# Sheet1.net
KiCad netlist of a schematic drawn in Altium Designer
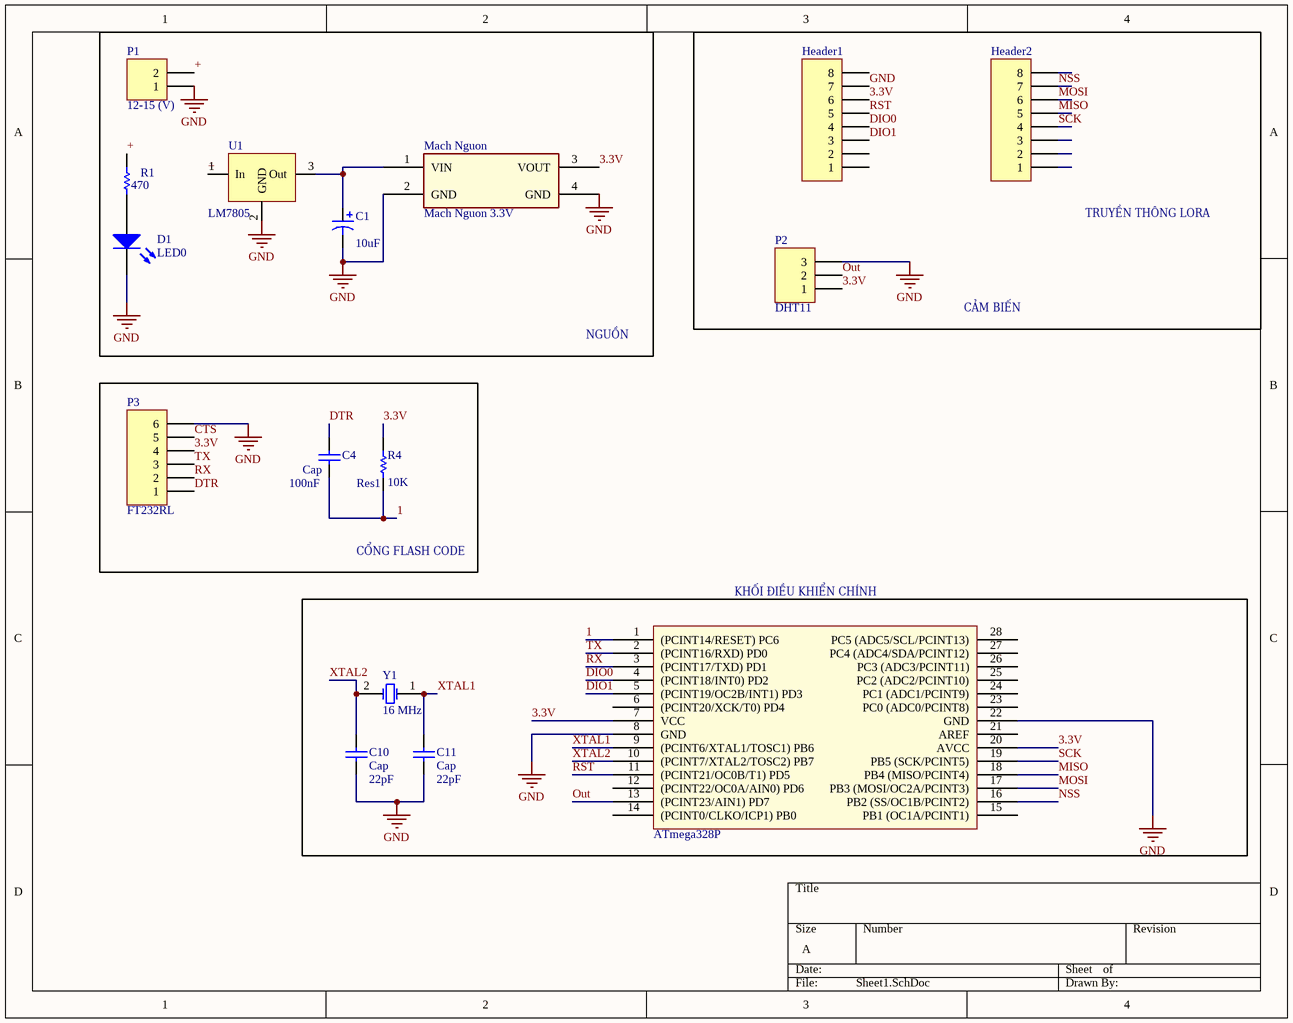
[diagram p0: Sheet1.SchDoc]

(export (version "E")
  (design (tool "Eeschema 10.0.6"))
  (components
    (comp (ref "ATmega328P")
      (value "ATmega328P")
      (footprint "DIP794W46P254L2967H457Q28B")
      (libsource (lib "ATMEGA328") (part "ATmega328P"))
    )
    (comp (ref "C1")
      (value "10uF")
      (footprint "RB7.6-15")
      (description "Polarized Capacitor (Radial)")
      (fields (field (name "Comment") "Cap Pol1") (field (name "PUBLISHER") "Altium Limited"))
      (libsource (lib "Miscellaneous Devices") (part "Cap Pol1"))
    )
    (comp (ref "C4")
      (value "Cap")
      (footprint "RAD-0.3")
      (description "Capacitor")
      (fields (field (name "ALTIUM_VALUE") "100nF") (field (name "PUBLISHER") "Altium Limited"))
      (libsource (lib "Miscellaneous Devices") (part "Cap"))
    )
    (comp (ref "C10")
      (value "Cap")
      (footprint "RAD-0.3")
      (description "Capacitor")
      (fields (field (name "ALTIUM_VALUE") "22pF") (field (name "PUBLISHER") "Altium Limited"))
      (libsource (lib "Miscellaneous Devices") (part "Cap"))
    )
    (comp (ref "C11")
      (value "Cap")
      (footprint "RAD-0.3")
      (description "Capacitor")
      (fields (field (name "ALTIUM_VALUE") "22pF") (field (name "PUBLISHER") "Altium Limited"))
      (libsource (lib "Miscellaneous Devices") (part "Cap"))
    )
    (comp (ref "D1")
      (value "LED0")
      (footprint "LED-0")
      (description "Typical INFRARED GaAs LED")
      (fields (field (name "PUBLISHER") "Altium Limited"))
      (libsource (lib "Miscellaneous Devices") (part "LED0"))
    )
    (comp (ref "Header1")
      (value "~")
      (footprint "HDR1X8")
      (description "Header, 8-Pin")
      (fields (field (name "PUBLISHER") "Altium Limited"))
      (libsource (lib "Miscellaneous Connectors") (part "Header 8"))
    )
    (comp (ref "Header2")
      (value "~")
      (footprint "HDR1X8")
      (description "Header, 8-Pin")
      (fields (field (name "PUBLISHER") "Altium Limited"))
      (libsource (lib "Miscellaneous Connectors") (part "Header 8"))
    )
    (comp (ref "Mach Nguon")
      (value "Mach Nguon 3.3V")
      (footprint "PCBComponent_1")
      (libsource (lib "MachNguon3.3V") (part "Component_1"))
    )
    (comp (ref "P1")
      (value "12-15 (V)")
      (footprint "HDR1X2")
      (description "Header, 2-Pin")
      (fields (field (name "PUBLISHER") "Altium Limited"))
      (libsource (lib "Miscellaneous Connectors") (part "Header 2"))
    )
    (comp (ref "P2")
      (value "DHT11")
      (footprint "HDR1X3")
      (description "Header, 3-Pin")
      (fields (field (name "PUBLISHER") "Altium Limited"))
      (libsource (lib "Miscellaneous Connectors") (part "Header 3"))
    )
    (comp (ref "P3")
      (value "FT232RL")
      (footprint "HDR1X6")
      (description "Header, 6-Pin")
      (fields (field (name "PUBLISHER") "Altium Limited"))
      (libsource (lib "Miscellaneous Connectors") (part "Header 6"))
    )
    (comp (ref "R1")
      (value "470")
      (footprint "AXIAL-0.3")
      (description "Resistor")
      (fields (field (name "Comment") "Res1") (field (name "PUBLISHER") "Altium Limited"))
      (libsource (lib "Miscellaneous Devices") (part "Res1"))
    )
    (comp (ref "R4")
      (value "Res1")
      (footprint "AXIAL-0.3")
      (description "Resistor")
      (fields (field (name "ALTIUM_VALUE") "10K") (field (name "PUBLISHER") "Altium Limited"))
      (libsource (lib "Miscellaneous Devices") (part "Res1"))
    )
    (comp (ref "U1")
      (value "LM7805")
      (footprint "TO92-")
      (description "IC REG LIN 5V 1A")
      (libsource (lib "LM7805") (part "LM7805"))
    )
    (comp (ref "Y1")
      (value "16 MHz")
      (footprint "R38")
      (description "Crystal Oscillator")
      (fields (field (name "PUBLISHER") "Altium Limited"))
      (libsource (lib "Miscellaneous Devices") (part "XTAL"))
    )
  )
  (nets
    (net (code "1") (name "/+") (class "Default")
      (node (ref "P1") (pin "2") (pinfunction "2_2") (pintype "passive"))
      (node (ref "R1") (pin "2") (pinfunction "2_2") (pintype "passive"))
      (node (ref "U1") (pin "1") (pinfunction "In_1") (pintype "passive"))
    )
    (net (code "2") (name "/1") (class "Default")
      (node (ref "ATmega328P") (pin "1") (pinfunction "(PCINT14/RESET)_PC6_1") (pintype "passive"))
      (node (ref "C4") (pin "1") (pinfunction "1_1") (pintype "passive"))
      (node (ref "R4") (pin "1") (pinfunction "1_1") (pintype "passive"))
    )
    (net (code "3") (name "/3.3V") (class "Default")
      (node (ref "ATmega328P") (pin "20") (pinfunction "AVCC_20") (pintype "passive"))
      (node (ref "ATmega328P") (pin "7") (pinfunction "VCC_7") (pintype "passive"))
      (node (ref "Header1") (pin "6") (pinfunction "6_6") (pintype "passive"))
      (node (ref "Mach Nguon") (pin "3") (pinfunction "VOUT_3") (pintype "passive"))
      (node (ref "P2") (pin "1") (pinfunction "1_1") (pintype "passive"))
      (node (ref "P3") (pin "4") (pinfunction "4_4") (pintype "passive"))
      (node (ref "R4") (pin "2") (pinfunction "2_2") (pintype "passive"))
    )
    (net (code "4") (name "/CTS") (class "Default")
      (node (ref "P3") (pin "5") (pinfunction "5_5") (pintype "passive"))
    )
    (net (code "5") (name "/DIO0") (class "Default")
      (node (ref "ATmega328P") (pin "4") (pinfunction "(PCINT18/INT0)_PD2_4") (pintype "passive"))
      (node (ref "Header1") (pin "4") (pinfunction "4_4") (pintype "passive"))
    )
    (net (code "6") (name "/DIO1") (class "Default")
      (node (ref "ATmega328P") (pin "5") (pinfunction "(PCINT19/OC2B/INT1)_PD3_5") (pintype "passive"))
      (node (ref "Header1") (pin "3") (pinfunction "3_3") (pintype "passive"))
    )
    (net (code "7") (name "/DTR") (class "Default")
      (node (ref "C4") (pin "2") (pinfunction "2_2") (pintype "passive"))
      (node (ref "P3") (pin "1") (pinfunction "1_1") (pintype "passive"))
    )
    (net (code "8") (name "/MISO") (class "Default")
      (node (ref "ATmega328P") (pin "18") (pinfunction "PB4_(MISO/PCINT4)_18") (pintype "passive"))
      (node (ref "Header2") (pin "5") (pinfunction "5_5") (pintype "passive"))
    )
    (net (code "9") (name "/MOSI") (class "Default")
      (node (ref "ATmega328P") (pin "17") (pinfunction "PB3_(MOSI/OC2A/PCINT3)_17") (pintype "passive"))
      (node (ref "Header2") (pin "6") (pinfunction "6_6") (pintype "passive"))
    )
    (net (code "10") (name "/NSS") (class "Default")
      (node (ref "ATmega328P") (pin "16") (pinfunction "PB2_(SS/OC1B/PCINT2)_16") (pintype "passive"))
      (node (ref "Header2") (pin "7") (pinfunction "7_7") (pintype "passive"))
    )
    (net (code "11") (name "/Out") (class "Default")
      (node (ref "ATmega328P") (pin "13") (pinfunction "(PCINT23/AIN1)_PD7_13") (pintype "passive"))
      (node (ref "P2") (pin "2") (pinfunction "2_2") (pintype "passive"))
    )
    (net (code "12") (name "/RST") (class "Default")
      (node (ref "ATmega328P") (pin "11") (pinfunction "(PCINT21/OC0B/T1)_PD5_11") (pintype "passive"))
      (node (ref "Header1") (pin "5") (pinfunction "5_5") (pintype "passive"))
    )
    (net (code "13") (name "/RX") (class "Default")
      (node (ref "ATmega328P") (pin "3") (pinfunction "(PCINT17/TXD)_PD1_3") (pintype "passive"))
      (node (ref "P3") (pin "2") (pinfunction "2_2") (pintype "passive"))
    )
    (net (code "14") (name "/SCK") (class "Default")
      (node (ref "ATmega328P") (pin "19") (pinfunction "PB5_(SCK/PCINT5)_19") (pintype "passive"))
      (node (ref "Header2") (pin "4") (pinfunction "4_4") (pintype "passive"))
    )
    (net (code "15") (name "/TX") (class "Default")
      (node (ref "ATmega328P") (pin "2") (pinfunction "(PCINT16/RXD)_PD0_2") (pintype "passive"))
      (node (ref "P3") (pin "3") (pinfunction "3_3") (pintype "passive"))
    )
    (net (code "16") (name "/XTAL1") (class "Default")
      (node (ref "ATmega328P") (pin "9") (pinfunction "(PCINT6/XTAL1/TOSC1)_PB6_9") (pintype "passive"))
      (node (ref "C11") (pin "2") (pinfunction "2_2") (pintype "passive"))
      (node (ref "Y1") (pin "1") (pinfunction "OSC1_1") (pintype "passive"))
    )
    (net (code "17") (name "/XTAL2") (class "Default")
      (node (ref "ATmega328P") (pin "10") (pinfunction "(PCINT7/XTAL2/TOSC2)_PB7_10") (pintype "passive"))
      (node (ref "C10") (pin "2") (pinfunction "2_2") (pintype "passive"))
      (node (ref "Y1") (pin "2") (pinfunction "OSC2_2") (pintype "passive"))
    )
    (net (code "18") (name "GND") (class "Default")
      (node (ref "ATmega328P") (pin "22") (pinfunction "GND_22") (pintype "passive"))
      (node (ref "ATmega328P") (pin "8") (pinfunction "GND_8") (pintype "passive"))
      (node (ref "C1") (pin "2") (pinfunction "2_2") (pintype "passive"))
      (node (ref "C10") (pin "1") (pinfunction "1_1") (pintype "passive"))
      (node (ref "C11") (pin "1") (pinfunction "1_1") (pintype "passive"))
      (node (ref "D1") (pin "2") (pinfunction "K_2") (pintype "passive"))
      (node (ref "Header1") (pin "7") (pinfunction "7_7") (pintype "passive"))
      (node (ref "Mach Nguon") (pin "2") (pinfunction "GND_2") (pintype "passive"))
      (node (ref "Mach Nguon") (pin "4") (pinfunction "GND_4") (pintype "passive"))
      (node (ref "P1") (pin "1") (pinfunction "1_1") (pintype "passive"))
      (node (ref "P2") (pin "3") (pinfunction "3_3") (pintype "passive"))
      (node (ref "P3") (pin "6") (pinfunction "6_6") (pintype "passive"))
      (node (ref "U1") (pin "2") (pinfunction "GND_2") (pintype "passive"))
    )
    (net (code "19") (name "Net-(D1-A)") (class "Default")
      (node (ref "D1") (pin "1") (pinfunction "A_1") (pintype "passive"))
      (node (ref "R1") (pin "1") (pinfunction "1_1") (pintype "passive"))
    )
    (net (code "20") (name "Net-(Mach Nguon-VIN)") (class "Default")
      (node (ref "C1") (pin "1") (pinfunction "1_1") (pintype "passive"))
      (node (ref "Mach Nguon") (pin "1") (pinfunction "VIN_1") (pintype "passive"))
      (node (ref "U1") (pin "3") (pinfunction "Out_3") (pintype "passive"))
    )
    (net (code "21") (name "unconnected-(ATmega328P-(PCINT0{slash}CLKO{slash}ICP1)_PB0-Pad14)") (class "Default")
      (node (ref "ATmega328P") (pin "14") (pinfunction "(PCINT0/CLKO/ICP1)_PB0_14") (pintype "passive"))
    )
    (net (code "22") (name "unconnected-(ATmega328P-(PCINT20{slash}XCK{slash}T0)_PD4-Pad6)") (class "Default")
      (node (ref "ATmega328P") (pin "6") (pinfunction "(PCINT20/XCK/T0)_PD4_6") (pintype "passive"))
    )
    (net (code "23") (name "unconnected-(ATmega328P-(PCINT22{slash}OC0A{slash}AIN0)_PD6-Pad12)") (class "Default")
      (node (ref "ATmega328P") (pin "12") (pinfunction "(PCINT22/OC0A/AIN0)_PD6_12") (pintype "passive"))
    )
    (net (code "24") (name "unconnected-(ATmega328P-AREF-Pad21)") (class "Default")
      (node (ref "ATmega328P") (pin "21") (pinfunction "AREF_21") (pintype "passive"))
    )
    (net (code "25") (name "unconnected-(ATmega328P-PB1_(OC1A{slash}PCINT1)-Pad15)") (class "Default")
      (node (ref "ATmega328P") (pin "15") (pinfunction "PB1_(OC1A/PCINT1)_15") (pintype "passive"))
    )
    (net (code "26") (name "unconnected-(ATmega328P-PC0_(ADC0{slash}PCINT8)-Pad23)") (class "Default")
      (node (ref "ATmega328P") (pin "23") (pinfunction "PC0_(ADC0/PCINT8)_23") (pintype "passive"))
    )
    (net (code "27") (name "unconnected-(ATmega328P-PC1_(ADC1{slash}PCINT9)-Pad24)") (class "Default")
      (node (ref "ATmega328P") (pin "24") (pinfunction "PC1_(ADC1/PCINT9)_24") (pintype "passive"))
    )
    (net (code "28") (name "unconnected-(ATmega328P-PC2_(ADC2{slash}PCINT10)-Pad25)") (class "Default")
      (node (ref "ATmega328P") (pin "25") (pinfunction "PC2_(ADC2/PCINT10)_25") (pintype "passive"))
    )
    (net (code "29") (name "unconnected-(ATmega328P-PC3_(ADC3{slash}PCINT11)-Pad26)") (class "Default")
      (node (ref "ATmega328P") (pin "26") (pinfunction "PC3_(ADC3/PCINT11)_26") (pintype "passive"))
    )
    (net (code "30") (name "unconnected-(ATmega328P-PC4_(ADC4{slash}SDA{slash}PCINT12)-Pad27)") (class "Default")
      (node (ref "ATmega328P") (pin "27") (pinfunction "PC4_(ADC4/SDA/PCINT12)_27") (pintype "passive"))
    )
    (net (code "31") (name "unconnected-(ATmega328P-PC5_(ADC5{slash}SCL{slash}PCINT13)-Pad28)") (class "Default")
      (node (ref "ATmega328P") (pin "28") (pinfunction "PC5_(ADC5/SCL/PCINT13)_28") (pintype "passive"))
    )
    (net (code "32") (name "unconnected-(Header1-Pad1)") (class "Default")
      (node (ref "Header1") (pin "1") (pinfunction "1_1") (pintype "passive"))
    )
    (net (code "33") (name "unconnected-(Header1-Pad2)") (class "Default")
      (node (ref "Header1") (pin "2") (pinfunction "2_2") (pintype "passive"))
    )
    (net (code "34") (name "unconnected-(Header1-Pad8)") (class "Default")
      (node (ref "Header1") (pin "8") (pinfunction "8_8") (pintype "passive"))
    )
    (net (code "35") (name "unconnected-(Header2-Pad1)") (class "Default")
      (node (ref "Header2") (pin "1") (pinfunction "1_1") (pintype "passive"))
    )
    (net (code "36") (name "unconnected-(Header2-Pad2)") (class "Default")
      (node (ref "Header2") (pin "2") (pinfunction "2_2") (pintype "passive"))
    )
    (net (code "37") (name "unconnected-(Header2-Pad3)") (class "Default")
      (node (ref "Header2") (pin "3") (pinfunction "3_3") (pintype "passive"))
    )
    (net (code "38") (name "unconnected-(Header2-Pad8)") (class "Default")
      (node (ref "Header2") (pin "8") (pinfunction "8_8") (pintype "passive"))
    )
  )
)
